# esquema.net
KiCad netlist of a schematic drawn in EAGLE
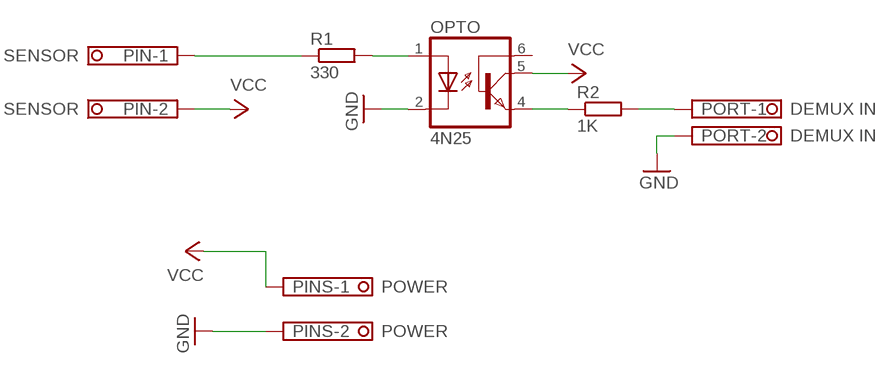
[diagram p0: schematic, sheet 1]

(export (version "E")
  (design (tool "Eeschema 10.0.6"))
  (components
    (comp (ref "OPTO")
      (value "4N25")
      (footprint "eagle-import:DIL06")
      (fields (field (name "MPN") "CNY17-1"))
      (libsource (lib "eagle-import") (part "CNY17"))
    )
    (comp (ref "PIN")
      (value "SENSOR")
      (footprint "eagle-import:TERMINAL-BLOCK-2-PIN-3.5MM-ROUND-PAD")
      (libsource (lib "eagle-import") (part "TERMINAL-BLOCK-3.5MM-2-PIN-ROUND-PAD"))
    )
    (comp (ref "PINS")
      (value "POWER")
      (footprint "eagle-import:TERMINAL-BLOCK-2-PIN-3.5MM-ROUND-PAD")
      (libsource (lib "eagle-import") (part "TERMINAL-BLOCK-3.5MM-2-PIN-ROUND-PAD"))
    )
    (comp (ref "PORT")
      (value "DEMUX IN")
      (footprint "eagle-import:TERMINAL-BLOCK-2-PIN-3.5MM-ROUND-PAD")
      (libsource (lib "eagle-import") (part "TERMINAL-BLOCK-3.5MM-2-PIN-ROUND-PAD"))
    )
    (comp (ref "R1")
      (value "330")
      (footprint "eagle-import:0204_7")
      (libsource (lib "eagle-import") (part "R-EU_0204/7"))
    )
    (comp (ref "R2")
      (value "1K")
      (footprint "eagle-import:0204_7")
      (libsource (lib "eagle-import") (part "R-EU_0204/7"))
    )
  )
  (nets
    (net (code "1") (name "GND") (class "Default")
      (node (ref "OPTO") (pin "2") (pinfunction "C_2") (pintype "passive"))
      (node (ref "PINS") (pin "2") (pinfunction "K_2") (pintype "passive"))
      (node (ref "PORT") (pin "2") (pinfunction "K_2") (pintype "passive"))
    )
    (net (code "2") (name "Net-(OPTO-A)") (class "Default")
      (node (ref "OPTO") (pin "1") (pinfunction "A_1") (pintype "passive"))
      (node (ref "R1") (pin "2") (pinfunction "2_2") (pintype "passive"))
    )
    (net (code "3") (name "Net-(OPTO-EMI)") (class "Default")
      (node (ref "OPTO") (pin "4") (pinfunction "EMI_4") (pintype "passive"))
      (node (ref "R2") (pin "1") (pinfunction "1_1") (pintype "passive"))
    )
    (net (code "4") (name "Net-(PINA-K)") (class "Default")
      (node (ref "PIN") (pin "1") (pinfunction "K_1") (pintype "passive"))
      (node (ref "R1") (pin "1") (pinfunction "1_1") (pintype "passive"))
    )
    (net (code "5") (name "Net-(PORTA-K)") (class "Default")
      (node (ref "PORT") (pin "1") (pinfunction "K_1") (pintype "passive"))
      (node (ref "R2") (pin "2") (pinfunction "2_2") (pintype "passive"))
    )
    (net (code "6") (name "VCC") (class "Default")
      (node (ref "OPTO") (pin "5") (pinfunction "COL_5") (pintype "passive"))
      (node (ref "PIN") (pin "2") (pinfunction "K_2") (pintype "passive"))
      (node (ref "PINS") (pin "1") (pinfunction "K_1") (pintype "passive"))
    )
    (net (code "7") (name "unconnected-(OPTO-BAS-Pad6)") (class "Default")
      (node (ref "OPTO") (pin "6") (pinfunction "BAS_6") (pintype "passive"))
    )
  )
)
